# PowerReplayUSBC.net
KiCad netlist of a schematic drawn in EAGLE
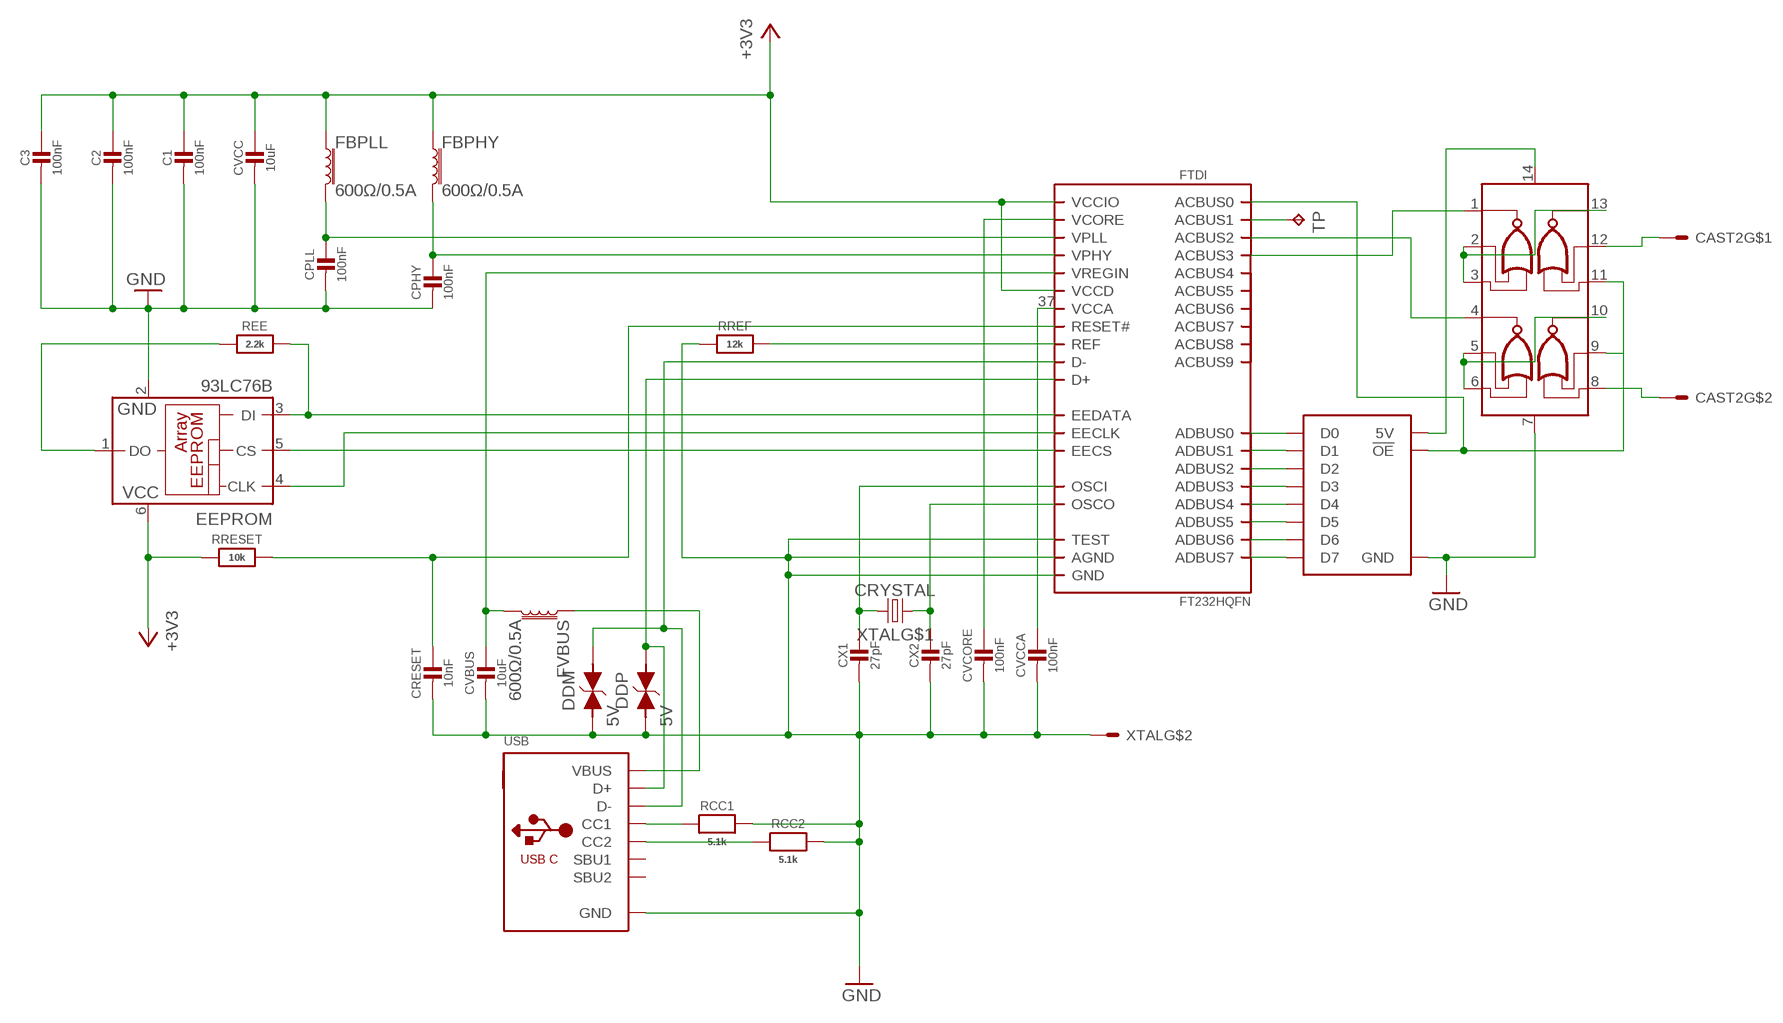
[diagram p0: schematic, sheet 1]

(export (version "E")
  (design (tool "Eeschema 10.0.6"))
  (components
    (comp (ref "C1")
      (value "100nF")
      (footprint "eagle-import:0603")
      (libsource (lib "eagle-import") (part "CAPACITOR0603"))
    )
    (comp (ref "C2")
      (value "100nF")
      (footprint "eagle-import:0603")
      (libsource (lib "eagle-import") (part "CAPACITOR0603"))
    )
    (comp (ref "C3")
      (value "100nF")
      (footprint "eagle-import:0603")
      (libsource (lib "eagle-import") (part "CAPACITOR0603"))
    )
    (comp (ref "CAST1")
      (value "BUFFER-CASTELLATION")
      (footprint "eagle-import:BUFFER-CASTELLATION")
      (libsource (lib "eagle-import") (part "BUFFER-CASTELLATION"))
    )
    (comp (ref "CAST2")
      (value "PLA-CASTELLATION")
      (footprint "eagle-import:PLA-CASTELLATION")
      (libsource (lib "eagle-import") (part "PLA-CASTELLATION"))
    )
    (comp (ref "CPHY")
      (value "100nF")
      (footprint "eagle-import:0603")
      (libsource (lib "eagle-import") (part "CAPACITOR0603"))
    )
    (comp (ref "CPLL")
      (value "100nF")
      (footprint "eagle-import:0603")
      (libsource (lib "eagle-import") (part "CAPACITOR0603"))
    )
    (comp (ref "CRESET")
      (value "10nF")
      (footprint "eagle-import:0603")
      (libsource (lib "eagle-import") (part "CAPACITOR0603"))
    )
    (comp (ref "CVBUS")
      (value "10uF")
      (footprint "eagle-import:1206")
      (libsource (lib "eagle-import") (part "CAPACITOR1206"))
    )
    (comp (ref "CVCC")
      (value "10uF")
      (footprint "eagle-import:1206")
      (libsource (lib "eagle-import") (part "CAPACITOR1206"))
    )
    (comp (ref "CVCCA")
      (value "100nF")
      (footprint "eagle-import:0603")
      (libsource (lib "eagle-import") (part "CAPACITOR0603"))
    )
    (comp (ref "CVCORE")
      (value "100nF")
      (footprint "eagle-import:0603")
      (libsource (lib "eagle-import") (part "CAPACITOR0603"))
    )
    (comp (ref "CX1")
      (value "27pF")
      (footprint "eagle-import:0402")
      (libsource (lib "eagle-import") (part "CAPACITOR0402"))
    )
    (comp (ref "CX2")
      (value "27pF")
      (footprint "eagle-import:0402")
      (libsource (lib "eagle-import") (part "CAPACITOR0402"))
    )
    (comp (ref "DDM")
      (value "5V")
      (footprint "eagle-import:WE-VE_0603")
      (libsource (lib "eagle-import") (part "WE-VE_0603_82356050050"))
    )
    (comp (ref "DDP")
      (value "5V")
      (footprint "eagle-import:WE-VE_0603")
      (libsource (lib "eagle-import") (part "WE-VE_0603_82356050050"))
    )
    (comp (ref "EEPROM")
      (value "93LC76B")
      (footprint "eagle-import:SOT23-6")
      (fields (field (name "MF") "MICROCHIP") (field (name "MPN") "93LC76BT-I/OT"))
      (libsource (lib "eagle-import") (part "9376?BLC"))
    )
    (comp (ref "FBPHY")
      (value "600Ω/0.5A")
      (footprint "eagle-import:0603")
      (libsource (lib "eagle-import") (part "FERRITE_BEAD-0603"))
    )
    (comp (ref "FBPLL")
      (value "600Ω/0.5A")
      (footprint "eagle-import:0603")
      (libsource (lib "eagle-import") (part "FERRITE_BEAD-0603"))
    )
    (comp (ref "FTDI")
      (value "FT232HQFN")
      (footprint "eagle-import:QFN48_8MM")
      (libsource (lib "eagle-import") (part "FT232HQFN"))
    )
    (comp (ref "FVBUS")
      (value "600Ω/0.5A")
      (footprint "eagle-import:0603")
      (libsource (lib "eagle-import") (part "FERRITE_BEAD-0603"))
    )
    (comp (ref "GATES")
      (value "7402TSSOP14")
      (footprint "eagle-import:TSSOP14-RU")
      (libsource (lib "eagle-import") (part "7402TSSOP14"))
    )
    (comp (ref "RCC1")
      (value "5.1k")
      (footprint "eagle-import:0402")
      (libsource (lib "eagle-import") (part "RESISTOR0402"))
    )
    (comp (ref "RCC2")
      (value "5.1k")
      (footprint "eagle-import:0402")
      (libsource (lib "eagle-import") (part "RESISTOR0402"))
    )
    (comp (ref "REE")
      (value "2.2k")
      (footprint "eagle-import:0603")
      (libsource (lib "eagle-import") (part "RESISTOR0603"))
    )
    (comp (ref "RREF")
      (value "12k")
      (footprint "eagle-import:0603")
      (libsource (lib "eagle-import") (part "RESISTOR0603"))
    )
    (comp (ref "RRESET")
      (value "10k")
      (footprint "eagle-import:0603")
      (libsource (lib "eagle-import") (part "RESISTOR0603"))
    )
    (comp (ref "TP") (value "TP") (footprint "eagle-import:TP") (libsource (lib "eagle-import") (part "TP")))
    (comp (ref "USB")
      (value "USB-C")
      (footprint "eagle-import:USB-C")
      (libsource (lib "eagle-import") (part "USB-C"))
    )
    (comp (ref "XTAL")
      (value "CRYSTAL")
      (footprint "eagle-import:SMD3225-4P")
      (libsource (lib "eagle-import") (part "CRYSTAL"))
    )
  )
  (nets
    (net (code "1") (name "+3V3") (class "Default")
      (node (ref "C1") (pin "1") (pinfunction "1_1") (pintype "passive"))
      (node (ref "C2") (pin "1") (pinfunction "1_1") (pintype "passive"))
      (node (ref "C3") (pin "1") (pinfunction "1_1") (pintype "passive"))
      (node (ref "CVCC") (pin "1") (pinfunction "1_1") (pintype "passive"))
      (node (ref "EEPROM") (pin "6") (pinfunction "VCC_6") (pintype "power_in"))
      (node (ref "FBPHY") (pin "1") (pinfunction "1_1") (pintype "passive"))
      (node (ref "FBPLL") (pin "1") (pinfunction "1_1") (pintype "passive"))
      (node (ref "FTDI") (pin "12") (pinfunction "VCCIO_12") (pintype "bidirectional"))
      (node (ref "FTDI") (pin "24") (pinfunction "VCCIO_24") (pintype "bidirectional"))
      (node (ref "FTDI") (pin "39") (pinfunction "VCCD_39") (pintype "bidirectional"))
      (node (ref "FTDI") (pin "46") (pinfunction "VCCIO_46") (pintype "bidirectional"))
      (node (ref "RRESET") (pin "1") (pinfunction "1_1") (pintype "passive"))
    )
    (net (code "2") (name "GND") (class "Default")
      (node (ref "C1") (pin "2") (pinfunction "2_2") (pintype "passive"))
      (node (ref "C2") (pin "2") (pinfunction "2_2") (pintype "passive"))
      (node (ref "C3") (pin "2") (pinfunction "2_2") (pintype "passive"))
      (node (ref "CAST1") (pin "P$9") (pinfunction "GND_P$9") (pintype "input"))
      (node (ref "CPHY") (pin "2") (pinfunction "2_2") (pintype "passive"))
      (node (ref "CPLL") (pin "2") (pinfunction "2_2") (pintype "passive"))
      (node (ref "CRESET") (pin "2") (pinfunction "2_2") (pintype "passive"))
      (node (ref "CVBUS") (pin "2") (pinfunction "2_2") (pintype "passive"))
      (node (ref "CVCC") (pin "2") (pinfunction "2_2") (pintype "passive"))
      (node (ref "CVCCA") (pin "2") (pinfunction "2_2") (pintype "passive"))
      (node (ref "CVCORE") (pin "2") (pinfunction "2_2") (pintype "passive"))
      (node (ref "CX1") (pin "2") (pinfunction "2_2") (pintype "passive"))
      (node (ref "CX2") (pin "2") (pinfunction "2_2") (pintype "passive"))
      (node (ref "DDM") (pin "2") (pinfunction "2_2") (pintype "passive"))
      (node (ref "DDP") (pin "2") (pinfunction "2_2") (pintype "passive"))
      (node (ref "EEPROM") (pin "2") (pinfunction "GND_2") (pintype "power_in"))
      (node (ref "FTDI") (pin "10") (pinfunction "GND_10") (pintype "bidirectional"))
      (node (ref "FTDI") (pin "11") (pinfunction "GND_11") (pintype "bidirectional"))
      (node (ref "FTDI") (pin "22") (pinfunction "GND_22") (pintype "bidirectional"))
      (node (ref "FTDI") (pin "23") (pinfunction "GND_23") (pintype "bidirectional"))
      (node (ref "FTDI") (pin "35") (pinfunction "GND_35") (pintype "bidirectional"))
      (node (ref "FTDI") (pin "36") (pinfunction "GND_36") (pintype "bidirectional"))
      (node (ref "FTDI") (pin "4") (pinfunction "AGND_4") (pintype "bidirectional"))
      (node (ref "FTDI") (pin "41") (pinfunction "AGND_41") (pintype "bidirectional"))
      (node (ref "FTDI") (pin "42") (pinfunction "TEST_42") (pintype "bidirectional"))
      (node (ref "FTDI") (pin "47") (pinfunction "GND_47") (pintype "bidirectional"))
      (node (ref "FTDI") (pin "48") (pinfunction "GND_48") (pintype "bidirectional"))
      (node (ref "FTDI") (pin "9") (pinfunction "AGND_9") (pintype "bidirectional"))
      (node (ref "FTDI") (pin "THERMAL") (pinfunction "GND_THERMAL") (pintype "bidirectional"))
      (node (ref "GATES") (pin "7") (pinfunction "P$7_7") (pintype "bidirectional"))
      (node (ref "RCC1") (pin "2") (pinfunction "2_2") (pintype "passive"))
      (node (ref "RCC2") (pin "2") (pinfunction "2_2") (pintype "passive"))
      (node (ref "RREF") (pin "1") (pinfunction "1_1") (pintype "passive"))
      (node (ref "USB") (pin "A1B12") (pinfunction "GND_A1B12") (pintype "power_in"))
      (node (ref "USB") (pin "B1A12") (pinfunction "GND_B1A12") (pintype "power_in"))
      (node (ref "USB") (pin "M1") (pinfunction "GND_M1") (pintype "power_in"))
      (node (ref "USB") (pin "M2") (pinfunction "GND_M2") (pintype "power_in"))
      (node (ref "USB") (pin "M3") (pinfunction "GND_M3") (pintype "power_in"))
      (node (ref "USB") (pin "M4") (pinfunction "GND_M4") (pintype "power_in"))
      (node (ref "XTAL") (pin "P$2") (pinfunction "S_P$2") (pintype "passive"))
      (node (ref "XTAL") (pin "P$4") (pinfunction "S_P$4") (pintype "passive"))
    )
    (net (code "3") (name "Net-(CAST1-5V)") (class "Default")
      (node (ref "CAST1") (pin "P$11") (pinfunction "5V_P$11") (pintype "input"))
      (node (ref "GATES") (pin "14") (pinfunction "P$14_14") (pintype "bidirectional"))
    )
    (net (code "4") (name "Net-(CAST1-D0)") (class "Default")
      (node (ref "CAST1") (pin "P$1") (pinfunction "D0_P$1") (pintype "input"))
      (node (ref "FTDI") (pin "13") (pinfunction "ADBUS0_13") (pintype "bidirectional"))
    )
    (net (code "5") (name "Net-(CAST1-D1)") (class "Default")
      (node (ref "CAST1") (pin "P$2") (pinfunction "D1_P$2") (pintype "input"))
      (node (ref "FTDI") (pin "14") (pinfunction "ADBUS1_14") (pintype "bidirectional"))
    )
    (net (code "6") (name "Net-(CAST1-D2)") (class "Default")
      (node (ref "CAST1") (pin "P$3") (pinfunction "D2_P$3") (pintype "input"))
      (node (ref "FTDI") (pin "15") (pinfunction "ADBUS2_15") (pintype "bidirectional"))
    )
    (net (code "7") (name "Net-(CAST1-D3)") (class "Default")
      (node (ref "CAST1") (pin "P$4") (pinfunction "D3_P$4") (pintype "input"))
      (node (ref "FTDI") (pin "16") (pinfunction "ADBUS3_16") (pintype "bidirectional"))
    )
    (net (code "8") (name "Net-(CAST1-D4)") (class "Default")
      (node (ref "CAST1") (pin "P$5") (pinfunction "D4_P$5") (pintype "input"))
      (node (ref "FTDI") (pin "17") (pinfunction "ADBUS4_17") (pintype "bidirectional"))
    )
    (net (code "9") (name "Net-(CAST1-D5)") (class "Default")
      (node (ref "CAST1") (pin "P$6") (pinfunction "D5_P$6") (pintype "input"))
      (node (ref "FTDI") (pin "18") (pinfunction "ADBUS5_18") (pintype "bidirectional"))
    )
    (net (code "10") (name "Net-(CAST1-D6)") (class "Default")
      (node (ref "CAST1") (pin "P$7") (pinfunction "D6_P$7") (pintype "input"))
      (node (ref "FTDI") (pin "19") (pinfunction "ADBUS6_19") (pintype "bidirectional"))
    )
    (net (code "11") (name "Net-(CAST1-D7)") (class "Default")
      (node (ref "CAST1") (pin "P$8") (pinfunction "D7_P$8") (pintype "input"))
      (node (ref "FTDI") (pin "20") (pinfunction "ADBUS7_20") (pintype "bidirectional"))
    )
    (net (code "12") (name "Net-(CAST1-~{OE})") (class "Default")
      (node (ref "CAST1") (pin "P$10") (pinfunction "~{OE}_P$10") (pintype "input"))
      (node (ref "FTDI") (pin "21") (pinfunction "ACBUS0_21") (pintype "bidirectional"))
      (node (ref "GATES") (pin "11") (pinfunction "P$11_11") (pintype "bidirectional"))
      (node (ref "GATES") (pin "9") (pinfunction "P$9_9") (pintype "bidirectional"))
    )
    (net (code "13") (name "Net-(CAST2A-S)") (class "Default")
      (node (ref "CAST2") (pin "P$1") (pinfunction "S_P$1") (pintype "passive"))
      (node (ref "GATES") (pin "12") (pinfunction "P$12_12") (pintype "bidirectional"))
    )
    (net (code "14") (name "Net-(CAST2B-S)") (class "Default")
      (node (ref "CAST2") (pin "P$2") (pinfunction "S_P$2") (pintype "passive"))
      (node (ref "GATES") (pin "8") (pinfunction "P$8_8") (pintype "bidirectional"))
    )
    (net (code "15") (name "Net-(EEPROM-CLK)") (class "Default")
      (node (ref "EEPROM") (pin "4") (pinfunction "CLK_4") (pintype "input"))
      (node (ref "FTDI") (pin "44") (pinfunction "EECLK_44") (pintype "bidirectional"))
    )
    (net (code "16") (name "Net-(EEPROM-CS)") (class "Default")
      (node (ref "EEPROM") (pin "5") (pinfunction "CS_5") (pintype "input"))
      (node (ref "FTDI") (pin "45") (pinfunction "EECS_45") (pintype "bidirectional"))
    )
    (net (code "17") (name "Net-(EEPROM-DI)") (class "Default")
      (node (ref "EEPROM") (pin "3") (pinfunction "DI_3") (pintype "input"))
      (node (ref "FTDI") (pin "43") (pinfunction "EEDATA_43") (pintype "bidirectional"))
      (node (ref "REE") (pin "2") (pinfunction "2_2") (pintype "passive"))
    )
    (net (code "18") (name "Net-(EEPROM-DO)") (class "Default")
      (node (ref "EEPROM") (pin "1") (pinfunction "DO_1") (pintype "tri_state"))
      (node (ref "REE") (pin "1") (pinfunction "1_1") (pintype "passive"))
    )
    (net (code "19") (name "Net-(FTDI-ACBUS1)") (class "Default")
      (node (ref "FTDI") (pin "25") (pinfunction "ACBUS1_25") (pintype "bidirectional"))
      (node (ref "TP") (pin "P$1") (pinfunction "TP_P$1") (pintype "input"))
    )
    (net (code "20") (name "Net-(FTDI-ACBUS2)") (class "Default")
      (node (ref "FTDI") (pin "26") (pinfunction "ACBUS2_26") (pintype "bidirectional"))
      (node (ref "GATES") (pin "4") (pinfunction "P$4_4") (pintype "bidirectional"))
    )
    (net (code "21") (name "Net-(FTDI-ACBUS3)") (class "Default")
      (node (ref "FTDI") (pin "27") (pinfunction "ACBUS3_27") (pintype "bidirectional"))
      (node (ref "GATES") (pin "1") (pinfunction "P$1_1") (pintype "bidirectional"))
    )
    (net (code "22") (name "Net-(FTDI-D+)") (class "Default")
      (node (ref "DDP") (pin "1") (pinfunction "1_1") (pintype "passive"))
      (node (ref "FTDI") (pin "7") (pinfunction "D+_7") (pintype "bidirectional"))
      (node (ref "USB") (pin "A6") (pinfunction "D+_A6") (pintype "bidirectional"))
      (node (ref "USB") (pin "B6") (pinfunction "D+_B6") (pintype "bidirectional"))
    )
    (net (code "23") (name "Net-(FTDI-D-)") (class "Default")
      (node (ref "DDM") (pin "1") (pinfunction "1_1") (pintype "passive"))
      (node (ref "FTDI") (pin "6") (pinfunction "D-_6") (pintype "bidirectional"))
      (node (ref "USB") (pin "A7") (pinfunction "D-_A7") (pintype "bidirectional"))
      (node (ref "USB") (pin "B7") (pinfunction "D-_B7") (pintype "bidirectional"))
    )
    (net (code "24") (name "Net-(FTDI-OSCI)") (class "Default")
      (node (ref "CX1") (pin "1") (pinfunction "1_1") (pintype "passive"))
      (node (ref "FTDI") (pin "1") (pinfunction "OSCI_1") (pintype "bidirectional"))
      (node (ref "XTAL") (pin "P$1") (pinfunction "X1_P$1") (pintype "passive"))
    )
    (net (code "25") (name "Net-(FTDI-OSCO)") (class "Default")
      (node (ref "CX2") (pin "1") (pinfunction "1_1") (pintype "passive"))
      (node (ref "FTDI") (pin "2") (pinfunction "OSCO_2") (pintype "bidirectional"))
      (node (ref "XTAL") (pin "P$3") (pinfunction "X2_P$3") (pintype "passive"))
    )
    (net (code "26") (name "Net-(FTDI-REF)") (class "Default")
      (node (ref "FTDI") (pin "5") (pinfunction "REF_5") (pintype "bidirectional"))
      (node (ref "RREF") (pin "2") (pinfunction "2_2") (pintype "passive"))
    )
    (net (code "27") (name "Net-(FTDI-RESET#)") (class "Default")
      (node (ref "CRESET") (pin "1") (pinfunction "1_1") (pintype "passive"))
      (node (ref "FTDI") (pin "34") (pinfunction "RESET#_34") (pintype "bidirectional"))
      (node (ref "RRESET") (pin "2") (pinfunction "2_2") (pintype "passive"))
    )
    (net (code "28") (name "Net-(FTDI-VCCA)") (class "Default")
      (node (ref "CVCCA") (pin "1") (pinfunction "1_1") (pintype "passive"))
      (node (ref "FTDI") (pin "37") (pinfunction "VCCA_37") (pintype "bidirectional"))
    )
    (net (code "29") (name "Net-(FTDI-VCORE)") (class "Default")
      (node (ref "CVCORE") (pin "1") (pinfunction "1_1") (pintype "passive"))
      (node (ref "FTDI") (pin "38") (pinfunction "VCORE_38") (pintype "bidirectional"))
    )
    (net (code "30") (name "Net-(FTDI-VPHY)") (class "Default")
      (node (ref "CPHY") (pin "1") (pinfunction "1_1") (pintype "passive"))
      (node (ref "FBPHY") (pin "2") (pinfunction "2_2") (pintype "passive"))
      (node (ref "FTDI") (pin "3") (pinfunction "VPHY_3") (pintype "bidirectional"))
    )
    (net (code "31") (name "Net-(FTDI-VPLL)") (class "Default")
      (node (ref "CPLL") (pin "1") (pinfunction "1_1") (pintype "passive"))
      (node (ref "FBPLL") (pin "2") (pinfunction "2_2") (pintype "passive"))
      (node (ref "FTDI") (pin "8") (pinfunction "VPLL_8") (pintype "bidirectional"))
    )
    (net (code "32") (name "Net-(FTDI-VREGIN)") (class "Default")
      (node (ref "CVBUS") (pin "1") (pinfunction "1_1") (pintype "passive"))
      (node (ref "FTDI") (pin "40") (pinfunction "VREGIN_40") (pintype "bidirectional"))
      (node (ref "FVBUS") (pin "2") (pinfunction "2_2") (pintype "passive"))
    )
    (net (code "33") (name "Net-(FVBUS-Pad1)") (class "Default")
      (node (ref "FVBUS") (pin "1") (pinfunction "1_1") (pintype "passive"))
      (node (ref "USB") (pin "A4B9") (pinfunction "VBUS_A4B9") (pintype "power_in"))
      (node (ref "USB") (pin "B4A9") (pinfunction "VBUS_B4A9") (pintype "power_in"))
    )
    (net (code "34") (name "Net-(GATES-P$10)") (class "Default")
      (node (ref "GATES") (pin "10") (pinfunction "P$10_10") (pintype "bidirectional"))
      (node (ref "GATES") (pin "5") (pinfunction "P$5_5") (pintype "bidirectional"))
      (node (ref "GATES") (pin "6") (pinfunction "P$6_6") (pintype "bidirectional"))
    )
    (net (code "35") (name "Net-(GATES-P$13)") (class "Default")
      (node (ref "GATES") (pin "13") (pinfunction "P$13_13") (pintype "bidirectional"))
      (node (ref "GATES") (pin "2") (pinfunction "P$2_2") (pintype "bidirectional"))
      (node (ref "GATES") (pin "3") (pinfunction "P$3_3") (pintype "bidirectional"))
    )
    (net (code "36") (name "Net-(USB-CC1)") (class "Default")
      (node (ref "RCC1") (pin "1") (pinfunction "1_1") (pintype "passive"))
      (node (ref "USB") (pin "A5") (pinfunction "CC1_A5") (pintype "bidirectional"))
    )
    (net (code "37") (name "Net-(USB-CC2)") (class "Default")
      (node (ref "RCC2") (pin "1") (pinfunction "1_1") (pintype "passive"))
      (node (ref "USB") (pin "B5") (pinfunction "CC2_B5") (pintype "bidirectional"))
    )
    (net (code "38") (name "unconnected-(FTDI-ACBUS4-Pad28)") (class "Default")
      (node (ref "FTDI") (pin "28") (pinfunction "ACBUS4_28") (pintype "bidirectional"))
    )
    (net (code "39") (name "unconnected-(FTDI-ACBUS5-Pad29)") (class "Default")
      (node (ref "FTDI") (pin "29") (pinfunction "ACBUS5_29") (pintype "bidirectional"))
    )
    (net (code "40") (name "unconnected-(FTDI-ACBUS6-Pad30)") (class "Default")
      (node (ref "FTDI") (pin "30") (pinfunction "ACBUS6_30") (pintype "bidirectional"))
    )
    (net (code "41") (name "unconnected-(FTDI-ACBUS7-Pad31)") (class "Default")
      (node (ref "FTDI") (pin "31") (pinfunction "ACBUS7_31") (pintype "bidirectional"))
    )
    (net (code "42") (name "unconnected-(FTDI-ACBUS8-Pad32)") (class "Default")
      (node (ref "FTDI") (pin "32") (pinfunction "ACBUS8_32") (pintype "bidirectional"))
    )
    (net (code "43") (name "unconnected-(FTDI-ACBUS9-Pad33)") (class "Default")
      (node (ref "FTDI") (pin "33") (pinfunction "ACBUS9_33") (pintype "bidirectional"))
    )
    (net (code "44") (name "unconnected-(USB-SBU1-PadA8)") (class "Default")
      (node (ref "USB") (pin "A8") (pinfunction "SBU1_A8") (pintype "bidirectional"))
    )
    (net (code "45") (name "unconnected-(USB-SBU2-PadB8)") (class "Default")
      (node (ref "USB") (pin "B8") (pinfunction "SBU2_B8") (pintype "bidirectional"))
    )
  )
)
